# esptoy_v1.net
KiCad netlist of a schematic drawn in EAGLE
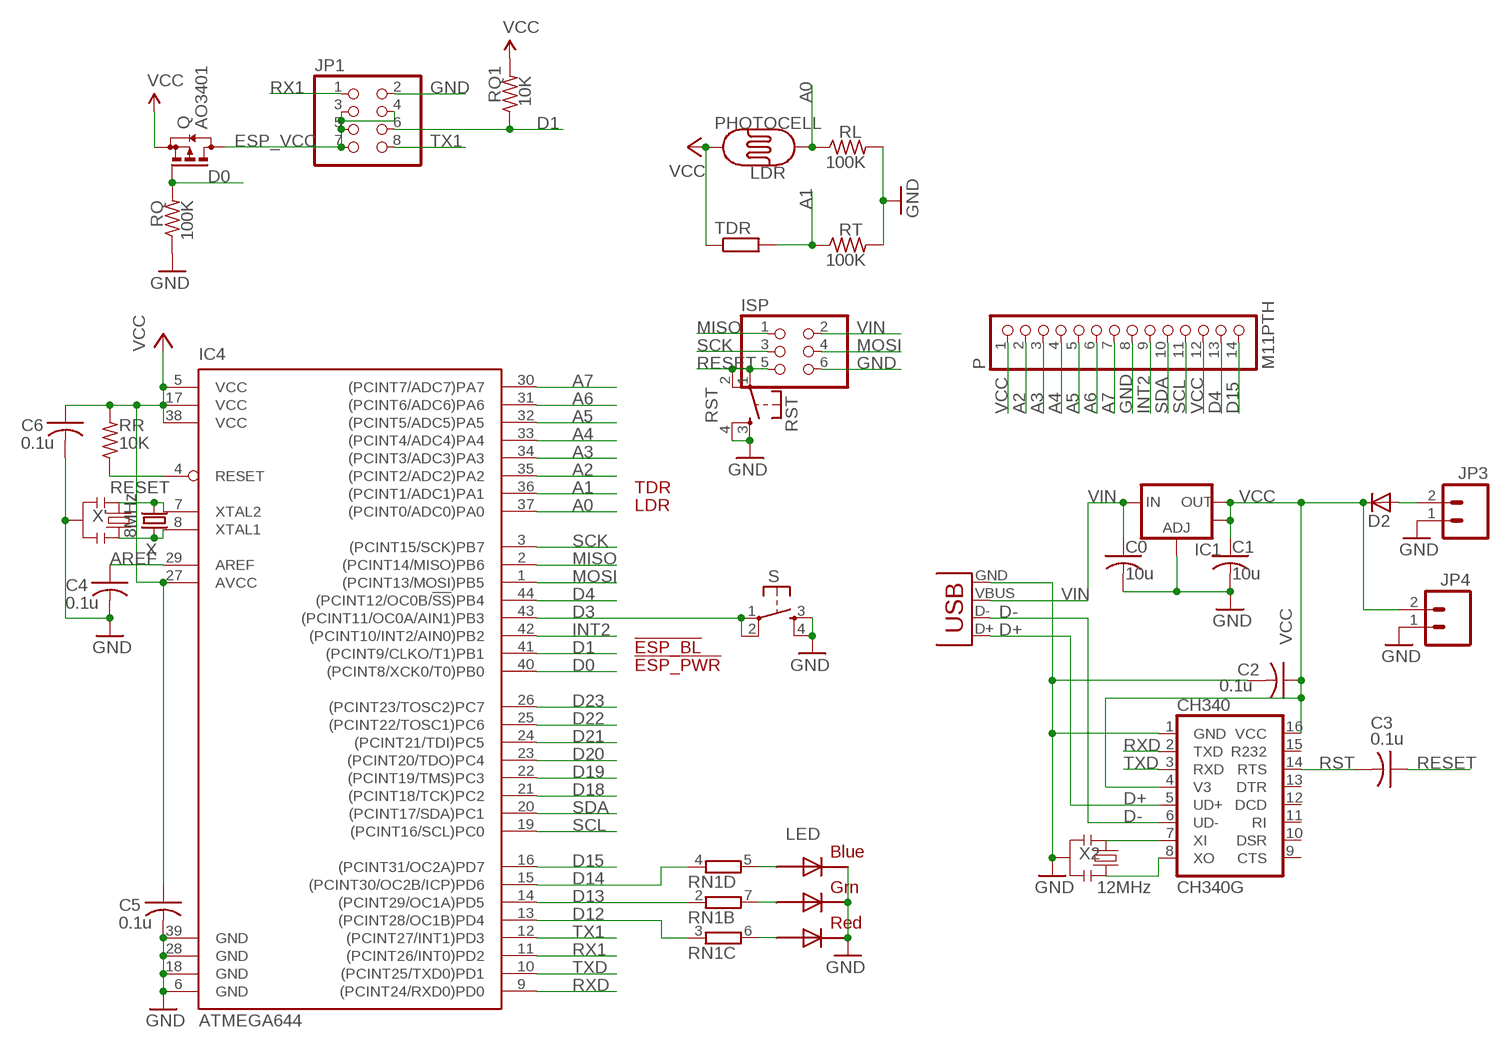
[diagram p0: schematic, sheet 1]

(export (version "E")
  (design (tool "Eeschema 10.0.6"))
  (components
    (comp (ref "C0")
      (value "10u")
      (footprint "eagle-import:C0805K")
      (libsource (lib "eagle-import") (part "adafruit2013_C-USC0805K"))
    )
    (comp (ref "C1")
      (value "10u")
      (footprint "eagle-import:C0805K")
      (libsource (lib "eagle-import") (part "adafruit2013_C-USC0805K"))
    )
    (comp (ref "C2")
      (value "0.1u")
      (footprint "eagle-import:C0603")
      (libsource (lib "eagle-import") (part "C-USC0603"))
    )
    (comp (ref "C3")
      (value "0.1u")
      (footprint "eagle-import:C0603")
      (libsource (lib "eagle-import") (part "C-USC0603"))
    )
    (comp (ref "C4")
      (value "0.1u")
      (footprint "eagle-import:C0603")
      (libsource (lib "eagle-import") (part "C-USC0603"))
    )
    (comp (ref "C5")
      (value "0.1u")
      (footprint "eagle-import:C0603K")
      (libsource (lib "eagle-import") (part "C-USC0603K"))
    )
    (comp (ref "C6")
      (value "0.1u")
      (footprint "eagle-import:C0603")
      (libsource (lib "eagle-import") (part "C-USC0603"))
    )
    (comp (ref "CH340")
      (value "CH340G")
      (footprint "eagle-import:SO16")
      (libsource (lib "eagle-import") (part "CH340G"))
    )
    (comp (ref "D2")
      (value "DIODESMA")
      (footprint "eagle-import:SMA-DIODE")
      (libsource (lib "eagle-import") (part "DIODESMA"))
    )
    (comp (ref "IC1")
      (value "V_REG_LM1117SOT223")
      (footprint "eagle-import:SOT223")
      (libsource (lib "eagle-import") (part "V_REG_LM1117SOT223"))
    )
    (comp (ref "IC4")
      (value "ATMEGA644")
      (footprint "eagle-import:TQFP44")
      (fields (field (name "MPN") "ATMEGA644PV-10AU"))
      (libsource (lib "eagle-import") (part "ATMEGA644A"))
    )
    (comp (ref "ISP")
      (value "PINHD-2X3")
      (footprint "eagle-import:2X03")
      (libsource (lib "eagle-import") (part "PINHD-2X3"))
    )
    (comp (ref "JP1")
      (value "PINHD-2X4")
      (footprint "eagle-import:2X04")
      (libsource (lib "eagle-import") (part "PINHD-2X4"))
    )
    (comp (ref "JP3")
      (value "M02-JST-2MM-SMT")
      (footprint "eagle-import:S2B-PH")
      (libsource (lib "eagle-import") (part "M02-JST-2MM-SMT"))
    )
    (comp (ref "JP4")
      (value "M02PTH")
      (footprint "eagle-import:1X02")
      (libsource (lib "eagle-import") (part "M02PTH"))
    )
    (comp (ref "LDR")
      (value "PHOTOCELL")
      (footprint "eagle-import:PHOTOCELL")
      (libsource (lib "eagle-import") (part "PHOTOCELLPTH"))
    )
    (comp (ref "LED")
      (value "RGBLED5050")
      (footprint "eagle-import:RGBLED5050")
      (libsource (lib "eagle-import") (part "RGBLED5050"))
    )
    (comp (ref "P")
      (value "M11PTH")
      (footprint "eagle-import:1X14-CB")
      (libsource (lib "eagle-import") (part "PINHD-1X14-CB"))
    )
    (comp (ref "Q")
      (value "AO3401")
      (footprint "eagle-import:SOT23")
      (libsource (lib "eagle-import") (part "BSS84"))
    )
    (comp (ref "RL")
      (value "100K")
      (footprint "eagle-import:R0805")
      (libsource (lib "eagle-import") (part "R-US_R0805"))
    )
    (comp (ref "RN1")
      (value "4R-NEXB38V")
      (footprint "eagle-import:EXB38V")
      (libsource (lib "eagle-import") (part "4R-NEXB38V"))
    )
    (comp (ref "RQ")
      (value "100K")
      (footprint "eagle-import:R0805")
      (libsource (lib "eagle-import") (part "R-US_R0805"))
    )
    (comp (ref "RQ1")
      (value "10K")
      (footprint "eagle-import:R0603")
      (libsource (lib "eagle-import") (part "R-US_R0603"))
    )
    (comp (ref "RR")
      (value "10K")
      (footprint "eagle-import:R0603")
      (libsource (lib "eagle-import") (part "R-US_R0603"))
    )
    (comp (ref "RST")
      (value "RST")
      (footprint "eagle-import:TACTILE_SWITCH_SMD")
      (libsource (lib "eagle-import") (part "TAC_SWITCHSMD"))
    )
    (comp (ref "RT")
      (value "100K")
      (footprint "eagle-import:R0805")
      (libsource (lib "eagle-import") (part "R-US_R0805"))
    )
    (comp (ref "S")
      (value "TAC_SWITCHSMD")
      (footprint "eagle-import:TACTILE_SWITCH_SMD")
      (libsource (lib "eagle-import") (part "TAC_SWITCHSMD"))
    )
    (comp (ref "TDR")
      (value "R-EU_V526-0")
      (footprint "eagle-import:V526-0")
      (libsource (lib "eagle-import") (part "R-EU_V526-0"))
    )
    (comp (ref "X")
      (value "8MHz")
      (footprint "eagle-import:TC26V")
      (libsource (lib "eagle-import") (part "CRYSTALTC26V"))
    )
    (comp (ref "X'")
      (value "12MHz")
      (footprint "eagle-import:RESONATOR-SMD")
      (libsource (lib "eagle-import") (part "RESONATORSMD"))
    )
    (comp (ref "X1")
      (value "USBSMD")
      (footprint "eagle-import:USB-MINIB")
      (libsource (lib "eagle-import") (part "USBSMD"))
    )
    (comp (ref "X2")
      (value "12MHz")
      (footprint "eagle-import:RESONATOR-SMD")
      (libsource (lib "eagle-import") (part "RESONATORSMD"))
    )
  )
  (nets
    (net (code "1") (name "/A0") (class "Default")
      (node (ref "IC4") (pin "37") (pinfunction "(PCINT0/ADC0)PA0_37") (pintype "bidirectional"))
      (node (ref "LDR") (pin "1") (pinfunction "P$1_1") (pintype "bidirectional"))
      (node (ref "RL") (pin "1") (pinfunction "1_1") (pintype "passive"))
    )
    (net (code "2") (name "/A1") (class "Default")
      (node (ref "IC4") (pin "36") (pinfunction "(PCINT1/ADC1)PA1_36") (pintype "bidirectional"))
      (node (ref "RT") (pin "1") (pinfunction "1_1") (pintype "passive"))
      (node (ref "TDR") (pin "2") (pinfunction "2_2") (pintype "passive"))
    )
    (net (code "3") (name "/A2") (class "Default")
      (node (ref "IC4") (pin "35") (pinfunction "(PCINT2/ADC2)PA2_35") (pintype "bidirectional"))
      (node (ref "P") (pin "2") (pinfunction "2_2") (pintype "passive"))
    )
    (net (code "4") (name "/A3") (class "Default")
      (node (ref "IC4") (pin "34") (pinfunction "(PCINT3/ADC3)PA3_34") (pintype "bidirectional"))
      (node (ref "P") (pin "3") (pinfunction "3_3") (pintype "passive"))
    )
    (net (code "5") (name "/A4") (class "Default")
      (node (ref "IC4") (pin "33") (pinfunction "(PCINT4/ADC4)PA4_33") (pintype "bidirectional"))
      (node (ref "P") (pin "4") (pinfunction "4_4") (pintype "passive"))
    )
    (net (code "6") (name "/A5") (class "Default")
      (node (ref "IC4") (pin "32") (pinfunction "(PCINT5/ADC5)PA5_32") (pintype "bidirectional"))
      (node (ref "P") (pin "5") (pinfunction "5_5") (pintype "passive"))
    )
    (net (code "7") (name "/A6") (class "Default")
      (node (ref "IC4") (pin "31") (pinfunction "(PCINT6/ADC6)PA6_31") (pintype "bidirectional"))
      (node (ref "P") (pin "6") (pinfunction "6_6") (pintype "passive"))
    )
    (net (code "8") (name "/A7") (class "Default")
      (node (ref "IC4") (pin "30") (pinfunction "(PCINT7/ADC7)PA7_30") (pintype "bidirectional"))
      (node (ref "P") (pin "7") (pinfunction "7_7") (pintype "passive"))
    )
    (net (code "9") (name "/AREF") (class "Default")
      (node (ref "C4") (pin "1") (pinfunction "1_1") (pintype "passive"))
      (node (ref "IC4") (pin "29") (pinfunction "AREF_29") (pintype "passive"))
    )
    (net (code "10") (name "/D+") (class "Default")
      (node (ref "CH340") (pin "5") (pinfunction "UD+_5") (pintype "bidirectional"))
      (node (ref "X1") (pin "D+") (pinfunction "D+_D+") (pintype "bidirectional"))
    )
    (net (code "11") (name "/D-") (class "Default")
      (node (ref "CH340") (pin "6") (pinfunction "UD-_6") (pintype "bidirectional"))
      (node (ref "X1") (pin "D-") (pinfunction "D-_D-") (pintype "bidirectional"))
    )
    (net (code "12") (name "/D0") (class "Default")
      (node (ref "IC4") (pin "40") (pinfunction "(PCINT8/XCK0/T0)PB0_40") (pintype "bidirectional"))
      (node (ref "Q") (pin "1") (pinfunction "G_1") (pintype "passive"))
      (node (ref "RQ") (pin "2") (pinfunction "2_2") (pintype "passive"))
    )
    (net (code "13") (name "/D1") (class "Default")
      (node (ref "IC4") (pin "41") (pinfunction "(PCINT9/CLKO/T1)PB1_41") (pintype "bidirectional"))
      (node (ref "JP1") (pin "6") (pinfunction "6_6") (pintype "passive"))
      (node (ref "RQ1") (pin "1") (pinfunction "1_1") (pintype "passive"))
    )
    (net (code "14") (name "/D3") (class "Default")
      (node (ref "IC4") (pin "43") (pinfunction "(PCINT11/OC0A/AIN1)PB3_43") (pintype "bidirectional"))
      (node (ref "S") (pin "1") (pinfunction "1_1") (pintype "passive"))
      (node (ref "S") (pin "2") (pinfunction "2_2") (pintype "passive"))
    )
    (net (code "15") (name "/D4") (class "Default")
      (node (ref "IC4") (pin "44") (pinfunction "(PCINT12/OC0B/~{SS})PB4_44") (pintype "bidirectional"))
      (node (ref "P") (pin "13") (pinfunction "13_13") (pintype "passive"))
    )
    (net (code "16") (name "/D12") (class "Default")
      (node (ref "IC4") (pin "13") (pinfunction "(PCINT28/OC1B)PD4_13") (pintype "bidirectional"))
      (node (ref "RN1") (pin "3") (pinfunction "1_3") (pintype "passive"))
    )
    (net (code "17") (name "/D13") (class "Default")
      (node (ref "IC4") (pin "14") (pinfunction "(PCINT29/OC1A)PD5_14") (pintype "bidirectional"))
      (node (ref "RN1") (pin "2") (pinfunction "1_2") (pintype "passive"))
    )
    (net (code "18") (name "/D14") (class "Default")
      (node (ref "IC4") (pin "15") (pinfunction "(PCINT30/OC2B/ICP)PD6_15") (pintype "bidirectional"))
      (node (ref "RN1") (pin "4") (pinfunction "1_4") (pintype "passive"))
    )
    (net (code "19") (name "/D15") (class "Default")
      (node (ref "IC4") (pin "16") (pinfunction "(PCINT31/OC2A)PD7_16") (pintype "bidirectional"))
      (node (ref "P") (pin "14") (pinfunction "14_14") (pintype "passive"))
    )
    (net (code "20") (name "/D18") (class "Default")
      (node (ref "IC4") (pin "21") (pinfunction "(PCINT18/TCK)PC2_21") (pintype "output"))
    )
    (net (code "21") (name "/D19") (class "Default")
      (node (ref "IC4") (pin "22") (pinfunction "(PCINT19/TMS)PC3_22") (pintype "output"))
    )
    (net (code "22") (name "/D20") (class "Default")
      (node (ref "IC4") (pin "23") (pinfunction "(PCINT20/TDO)PC4_23") (pintype "output"))
    )
    (net (code "23") (name "/D21") (class "Default")
      (node (ref "IC4") (pin "24") (pinfunction "(PCINT21/TDI)PC5_24") (pintype "output"))
    )
    (net (code "24") (name "/D22") (class "Default")
      (node (ref "IC4") (pin "25") (pinfunction "(PCINT22/TOSC1)PC6_25") (pintype "output"))
    )
    (net (code "25") (name "/D23") (class "Default")
      (node (ref "IC4") (pin "26") (pinfunction "(PCINT23/TOSC2)PC7_26") (pintype "output"))
    )
    (net (code "26") (name "/ESP_VCC") (class "Default")
      (node (ref "JP1") (pin "3") (pinfunction "3_3") (pintype "passive"))
      (node (ref "JP1") (pin "4") (pinfunction "4_4") (pintype "passive"))
      (node (ref "JP1") (pin "5") (pinfunction "5_5") (pintype "passive"))
      (node (ref "JP1") (pin "7") (pinfunction "7_7") (pintype "passive"))
      (node (ref "Q") (pin "3") (pinfunction "D_3") (pintype "passive"))
    )
    (net (code "27") (name "/INT2") (class "Default")
      (node (ref "IC4") (pin "42") (pinfunction "(PCINT10/INT2/AIN0)PB2_42") (pintype "bidirectional"))
      (node (ref "P") (pin "9") (pinfunction "9_9") (pintype "passive"))
    )
    (net (code "28") (name "/MISO") (class "Default")
      (node (ref "IC4") (pin "2") (pinfunction "(PCINT14/MISO)PB6_2") (pintype "bidirectional"))
      (node (ref "ISP") (pin "1") (pinfunction "1_1") (pintype "passive"))
    )
    (net (code "29") (name "/MOSI") (class "Default")
      (node (ref "IC4") (pin "1") (pinfunction "(PCINT13/MOSI)PB5_1") (pintype "bidirectional"))
      (node (ref "ISP") (pin "4") (pinfunction "4_4") (pintype "passive"))
    )
    (net (code "30") (name "/RESET") (class "Default")
      (node (ref "C3") (pin "1") (pinfunction "1_1") (pintype "passive"))
      (node (ref "IC4") (pin "4") (pinfunction "RESET_4") (pintype "input"))
      (node (ref "ISP") (pin "5") (pinfunction "5_5") (pintype "passive"))
      (node (ref "RR") (pin "1") (pinfunction "1_1") (pintype "passive"))
      (node (ref "RST") (pin "1") (pinfunction "1_1") (pintype "passive"))
      (node (ref "RST") (pin "2") (pinfunction "2_2") (pintype "passive"))
    )
    (net (code "31") (name "/RST") (class "Default")
      (node (ref "C3") (pin "2") (pinfunction "2_2") (pintype "passive"))
      (node (ref "CH340") (pin "14") (pinfunction "RTS_14") (pintype "bidirectional"))
    )
    (net (code "32") (name "/RX1") (class "Default")
      (node (ref "IC4") (pin "11") (pinfunction "(PCINT26/INT0)PD2_11") (pintype "bidirectional"))
      (node (ref "JP1") (pin "1") (pinfunction "1_1") (pintype "passive"))
    )
    (net (code "33") (name "/RXD") (class "Default")
      (node (ref "CH340") (pin "2") (pinfunction "TXD_2") (pintype "bidirectional"))
      (node (ref "IC4") (pin "9") (pinfunction "(PCINT24/RXD0)PD0_9") (pintype "bidirectional"))
    )
    (net (code "34") (name "/SCK") (class "Default")
      (node (ref "IC4") (pin "3") (pinfunction "(PCINT15/SCK)PB7_3") (pintype "bidirectional"))
      (node (ref "ISP") (pin "3") (pinfunction "3_3") (pintype "passive"))
    )
    (net (code "35") (name "/SCL") (class "Default")
      (node (ref "IC4") (pin "19") (pinfunction "(PCINT16/SCL)PC0_19") (pintype "output"))
      (node (ref "P") (pin "11") (pinfunction "11_11") (pintype "passive"))
    )
    (net (code "36") (name "/SDA") (class "Default")
      (node (ref "IC4") (pin "20") (pinfunction "(PCINT17/SDA)PC1_20") (pintype "output"))
      (node (ref "P") (pin "10") (pinfunction "10_10") (pintype "passive"))
    )
    (net (code "37") (name "/TX1") (class "Default")
      (node (ref "IC4") (pin "12") (pinfunction "(PCINT27/INT1)PD3_12") (pintype "bidirectional"))
      (node (ref "JP1") (pin "8") (pinfunction "8_8") (pintype "passive"))
    )
    (net (code "38") (name "/TXD") (class "Default")
      (node (ref "CH340") (pin "3") (pinfunction "RXD_3") (pintype "bidirectional"))
      (node (ref "IC4") (pin "10") (pinfunction "(PCINT25/TXD0)PD1_10") (pintype "bidirectional"))
    )
    (net (code "39") (name "/VIN") (class "Default")
      (node (ref "C0") (pin "1") (pinfunction "1_1") (pintype "passive"))
      (node (ref "IC1") (pin "3") (pinfunction "IN_3") (pintype "input"))
      (node (ref "ISP") (pin "2") (pinfunction "2_2") (pintype "passive"))
      (node (ref "X1") (pin "VBUS") (pinfunction "VBUS_VBUS") (pintype "bidirectional"))
    )
    (net (code "40") (name "GND") (class "Default")
      (node (ref "C0") (pin "2") (pinfunction "2_2") (pintype "passive"))
      (node (ref "C1") (pin "2") (pinfunction "2_2") (pintype "passive"))
      (node (ref "C2") (pin "2") (pinfunction "2_2") (pintype "passive"))
      (node (ref "C4") (pin "2") (pinfunction "2_2") (pintype "passive"))
      (node (ref "C5") (pin "2") (pinfunction "2_2") (pintype "passive"))
      (node (ref "C6") (pin "2") (pinfunction "2_2") (pintype "passive"))
      (node (ref "CH340") (pin "1") (pinfunction "GND_1") (pintype "power_in"))
      (node (ref "IC1") (pin "1") (pinfunction "ADJ_1") (pintype "input"))
      (node (ref "IC4") (pin "18") (pinfunction "GND_18") (pintype "power_in"))
      (node (ref "IC4") (pin "28") (pinfunction "GND_28") (pintype "power_in"))
      (node (ref "IC4") (pin "39") (pinfunction "GND_39") (pintype "power_in"))
      (node (ref "IC4") (pin "6") (pinfunction "GND_6") (pintype "power_in"))
      (node (ref "ISP") (pin "6") (pinfunction "6_6") (pintype "passive"))
      (node (ref "JP1") (pin "2") (pinfunction "2_2") (pintype "passive"))
      (node (ref "JP3") (pin "1") (pinfunction "1_1") (pintype "passive"))
      (node (ref "JP4") (pin "1") (pinfunction "1_1") (pintype "passive"))
      (node (ref "LED") (pin "4") (pinfunction "BLUE_C_4") (pintype "bidirectional"))
      (node (ref "LED") (pin "5") (pinfunction "RED_C_5") (pintype "bidirectional"))
      (node (ref "LED") (pin "6") (pinfunction "GREEN_C_6") (pintype "bidirectional"))
      (node (ref "P") (pin "8") (pinfunction "8_8") (pintype "passive"))
      (node (ref "RL") (pin "2") (pinfunction "2_2") (pintype "passive"))
      (node (ref "RQ") (pin "1") (pinfunction "1_1") (pintype "passive"))
      (node (ref "RST") (pin "3") (pinfunction "3_3") (pintype "passive"))
      (node (ref "RST") (pin "4") (pinfunction "4_4") (pintype "passive"))
      (node (ref "RT") (pin "2") (pinfunction "2_2") (pintype "passive"))
      (node (ref "S") (pin "3") (pinfunction "3_3") (pintype "passive"))
      (node (ref "S") (pin "4") (pinfunction "4_4") (pintype "passive"))
      (node (ref "X'") (pin "2") (pinfunction "2_2") (pintype "passive"))
      (node (ref "X1") (pin "GND") (pinfunction "GND_GND") (pintype "bidirectional"))
      (node (ref "X2") (pin "2") (pinfunction "2_2") (pintype "passive"))
    )
    (net (code "41") (name "Net-(CH340-XI)") (class "Default")
      (node (ref "CH340") (pin "7") (pinfunction "XI_7") (pintype "bidirectional"))
      (node (ref "X2") (pin "1") (pinfunction "1_1") (pintype "passive"))
    )
    (net (code "42") (name "Net-(CH340-XO)") (class "Default")
      (node (ref "CH340") (pin "8") (pinfunction "XO_8") (pintype "bidirectional"))
      (node (ref "X2") (pin "3") (pinfunction "3_3") (pintype "passive"))
    )
    (net (code "43") (name "Net-(D2-PadA)") (class "Default")
      (node (ref "D2") (pin "A") (pinfunction "A_A") (pintype "passive"))
      (node (ref "JP3") (pin "2") (pinfunction "2_2") (pintype "passive"))
    )
    (net (code "44") (name "Net-(IC4-XTAL1)") (class "Default")
      (node (ref "IC4") (pin "8") (pinfunction "XTAL1_8") (pintype "bidirectional"))
      (node (ref "X") (pin "1") (pinfunction "1_1") (pintype "passive"))
      (node (ref "X'") (pin "3") (pinfunction "3_3") (pintype "passive"))
    )
    (net (code "45") (name "Net-(IC4-XTAL2)") (class "Default")
      (node (ref "IC4") (pin "7") (pinfunction "XTAL2_7") (pintype "bidirectional"))
      (node (ref "X") (pin "2") (pinfunction "2_2") (pintype "passive"))
      (node (ref "X'") (pin "1") (pinfunction "1_1") (pintype "passive"))
    )
    (net (code "46") (name "Net-(LED-BLUE_A)") (class "Default")
      (node (ref "LED") (pin "3") (pinfunction "BLUE_A_3") (pintype "bidirectional"))
      (node (ref "RN1") (pin "5") (pinfunction "2_5") (pintype "passive"))
    )
    (net (code "47") (name "Net-(LED-GREEN_A)") (class "Default")
      (node (ref "LED") (pin "1") (pinfunction "GREEN_A_1") (pintype "bidirectional"))
      (node (ref "RN1") (pin "7") (pinfunction "2_7") (pintype "passive"))
    )
    (net (code "48") (name "Net-(LED-RED_A)") (class "Default")
      (node (ref "LED") (pin "2") (pinfunction "RED_A_2") (pintype "bidirectional"))
      (node (ref "RN1") (pin "6") (pinfunction "2_6") (pintype "passive"))
    )
    (net (code "49") (name "VCC") (class "Default")
      (node (ref "C1") (pin "1") (pinfunction "1_1") (pintype "passive"))
      (node (ref "C2") (pin "1") (pinfunction "1_1") (pintype "passive"))
      (node (ref "C5") (pin "1") (pinfunction "1_1") (pintype "passive"))
      (node (ref "C6") (pin "1") (pinfunction "1_1") (pintype "passive"))
      (node (ref "CH340") (pin "16") (pinfunction "VCC_16") (pintype "power_in"))
      (node (ref "CH340") (pin "4") (pinfunction "V3_4") (pintype "bidirectional"))
      (node (ref "D2") (pin "C") (pinfunction "C_C") (pintype "passive"))
      (node (ref "IC1") (pin "2") (pinfunction "OUT_2") (pintype "bidirectional"))
      (node (ref "IC1") (pin "4") (pinfunction "OUT_4") (pintype "bidirectional"))
      (node (ref "IC4") (pin "17") (pinfunction "VCC_17") (pintype "power_in"))
      (node (ref "IC4") (pin "27") (pinfunction "AVCC_27") (pintype "power_in"))
      (node (ref "IC4") (pin "38") (pinfunction "VCC_38") (pintype "power_in"))
      (node (ref "IC4") (pin "5") (pinfunction "VCC_5") (pintype "power_in"))
      (node (ref "JP4") (pin "2") (pinfunction "2_2") (pintype "passive"))
      (node (ref "LDR") (pin "2") (pinfunction "P$2_2") (pintype "bidirectional"))
      (node (ref "P") (pin "1") (pinfunction "1_1") (pintype "passive"))
      (node (ref "P") (pin "12") (pinfunction "12_12") (pintype "passive"))
      (node (ref "Q") (pin "2") (pinfunction "S_2") (pintype "passive"))
      (node (ref "RQ1") (pin "2") (pinfunction "2_2") (pintype "passive"))
      (node (ref "RR") (pin "2") (pinfunction "2_2") (pintype "passive"))
      (node (ref "TDR") (pin "1") (pinfunction "1_1") (pintype "passive"))
    )
    (net (code "50") (name "unconnected-(CH340-CTS-Pad9)") (class "Default")
      (node (ref "CH340") (pin "9") (pinfunction "CTS_9") (pintype "bidirectional"))
    )
    (net (code "51") (name "unconnected-(CH340-DCD-Pad12)") (class "Default")
      (node (ref "CH340") (pin "12") (pinfunction "DCD_12") (pintype "bidirectional"))
    )
    (net (code "52") (name "unconnected-(CH340-DSR-Pad10)") (class "Default")
      (node (ref "CH340") (pin "10") (pinfunction "DSR_10") (pintype "bidirectional"))
    )
    (net (code "53") (name "unconnected-(CH340-DTR-Pad13)") (class "Default")
      (node (ref "CH340") (pin "13") (pinfunction "DTR_13") (pintype "bidirectional"))
    )
    (net (code "54") (name "unconnected-(CH340-R232-Pad15)") (class "Default")
      (node (ref "CH340") (pin "15") (pinfunction "R232_15") (pintype "bidirectional"))
    )
    (net (code "55") (name "unconnected-(CH340-RI-Pad11)") (class "Default")
      (node (ref "CH340") (pin "11") (pinfunction "RI_11") (pintype "bidirectional"))
    )
  )
)
